# MainBoardV2.net
KiCad netlist of a schematic drawn in EAGLE
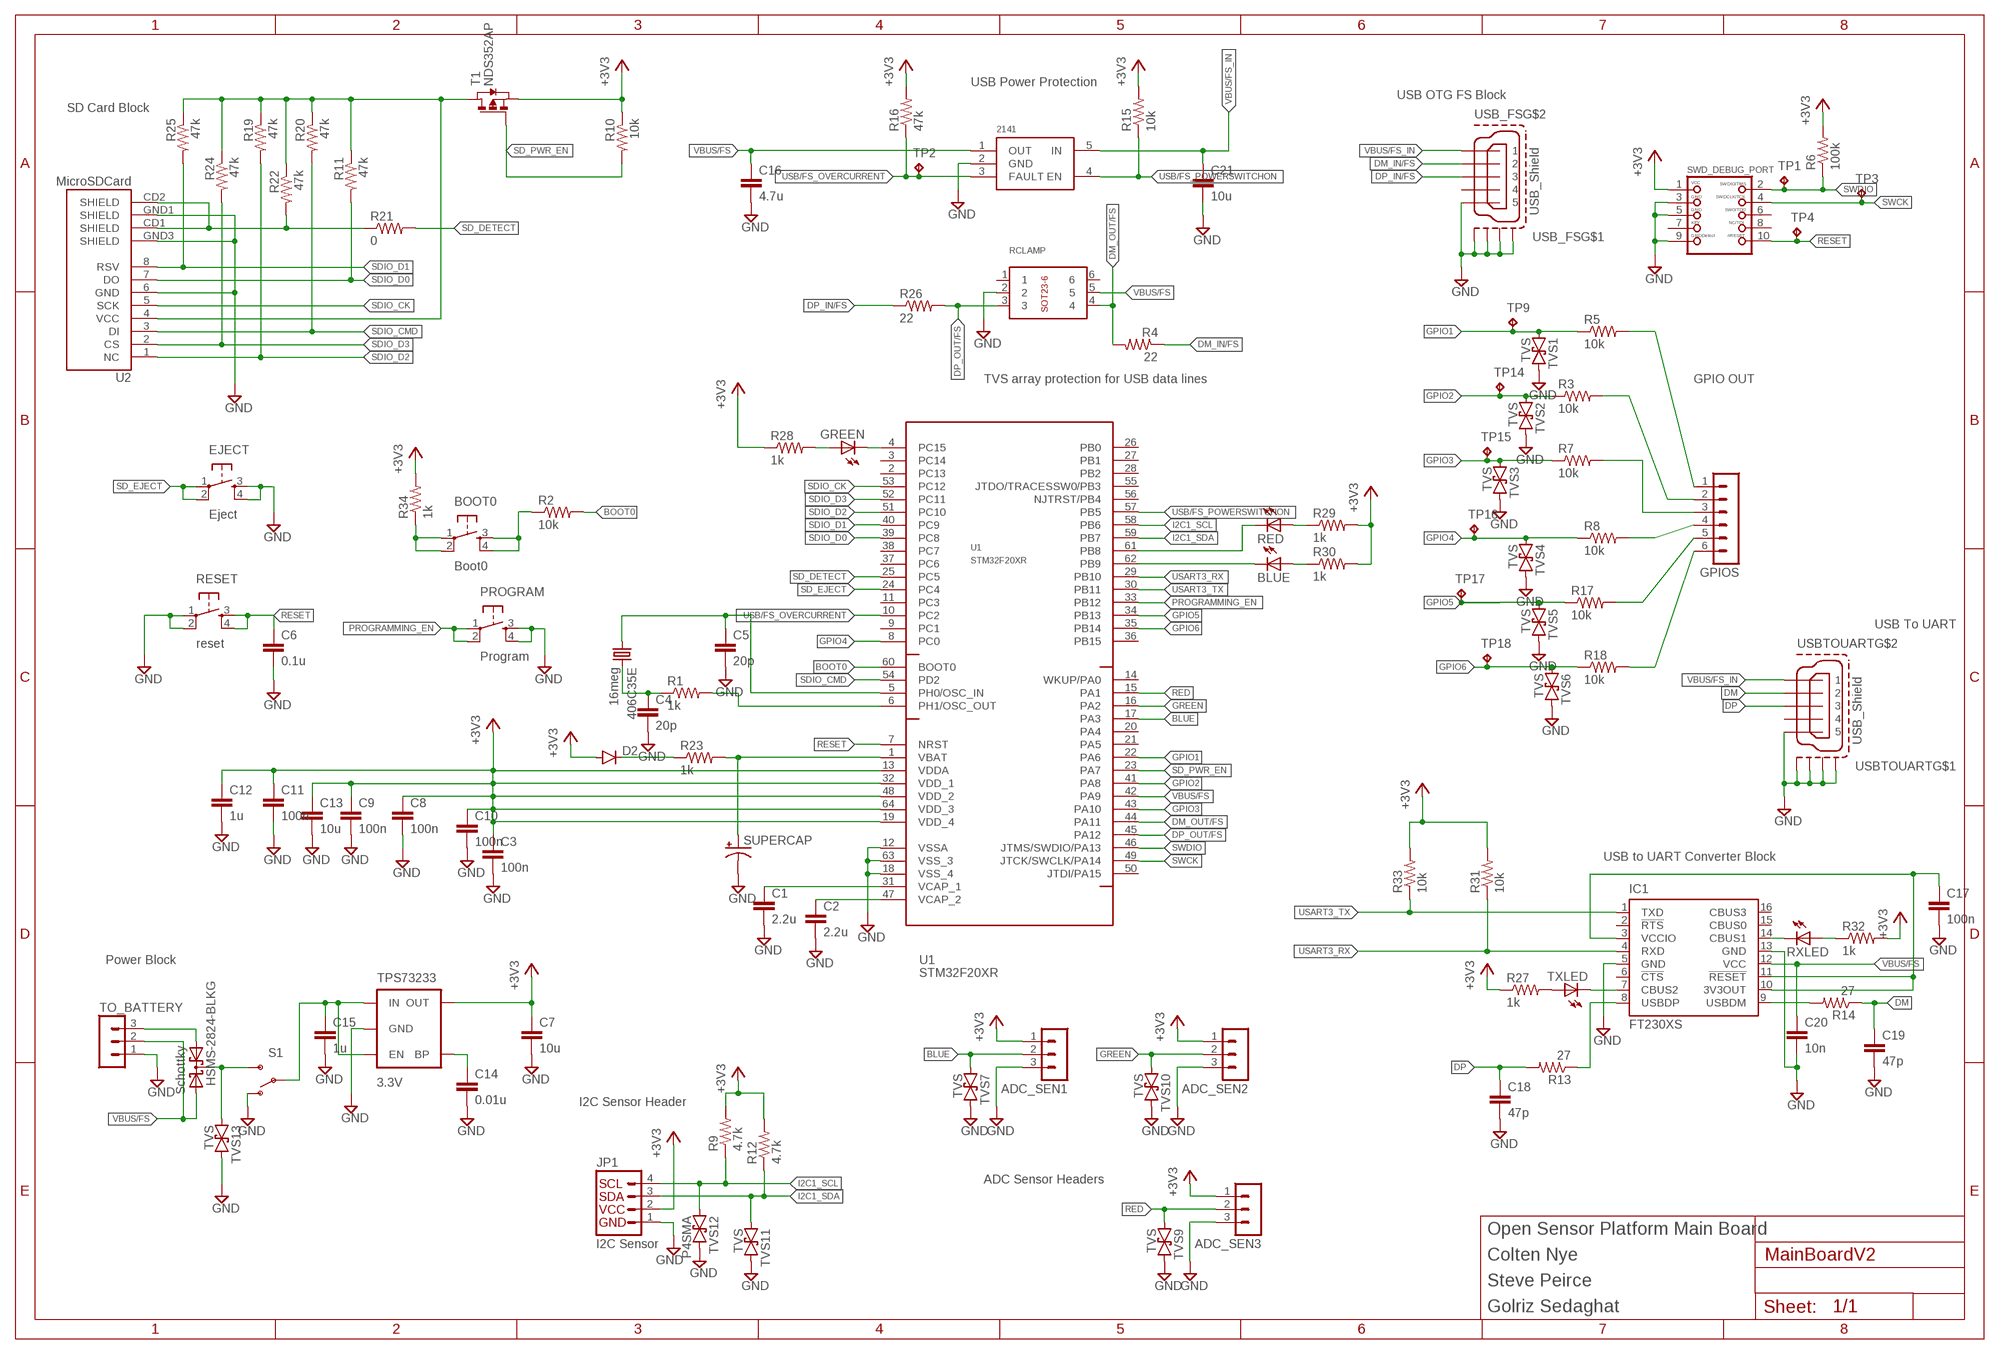
[diagram p0: schematic, sheet 1]

(export (version "E")
  (design (tool "Eeschema 10.0.6"))
  (components
    (comp (ref "406C35E")
      (value "16meg")
      (footprint "eagle-import:CTS406")
      (libsource (lib "eagle-import") (part "CRYSTALCTS406"))
    )
    (comp (ref "2141")
      (value "NCP1400A_STEPUP")
      (footprint "eagle-import:SOT23-5")
      (libsource (lib "eagle-import") (part "NCP1400A_STEPUP"))
    )
    (comp (ref "ADC_SEN1")
      (value "MA03-1")
      (footprint "eagle-import:MA03-1")
      (libsource (lib "eagle-import") (part "MA03-1"))
    )
    (comp (ref "ADC_SEN2")
      (value "MA03-1")
      (footprint "eagle-import:MA03-1")
      (libsource (lib "eagle-import") (part "MA03-1"))
    )
    (comp (ref "ADC_SEN3")
      (value "MA03-1")
      (footprint "eagle-import:MA03-1")
      (libsource (lib "eagle-import") (part "MA03-1"))
    )
    (comp (ref "BLUE")
      (value "LEDSML0805")
      (footprint "eagle-import:SML0805")
      (libsource (lib "eagle-import") (part "LEDSML0805"))
    )
    (comp (ref "BOOT0")
      (value "Boot0")
      (footprint "eagle-import:TACTILE-SWITCH-SMD")
      (libsource (lib "eagle-import") (part "TAC_SWITCHSMD"))
    )
    (comp (ref "C1")
      (value "2.2u")
      (footprint "eagle-import:C0805")
      (libsource (lib "eagle-import") (part "C-EUC0805"))
    )
    (comp (ref "C2")
      (value "2.2u")
      (footprint "eagle-import:C0805")
      (libsource (lib "eagle-import") (part "C-EUC0805"))
    )
    (comp (ref "C3")
      (value "100n")
      (footprint "eagle-import:C0805")
      (libsource (lib "eagle-import") (part "C-EUC0805"))
    )
    (comp (ref "C4")
      (value "20p")
      (footprint "eagle-import:C0805")
      (libsource (lib "eagle-import") (part "C-EUC0805"))
    )
    (comp (ref "C5")
      (value "20p")
      (footprint "eagle-import:C0805")
      (libsource (lib "eagle-import") (part "C-EUC0805"))
    )
    (comp (ref "C6")
      (value "0.1u")
      (footprint "eagle-import:C0805")
      (libsource (lib "eagle-import") (part "C-EUC0805"))
    )
    (comp (ref "C7")
      (value "10u")
      (footprint "eagle-import:C0805")
      (libsource (lib "eagle-import") (part "C-EUC0805"))
    )
    (comp (ref "C8")
      (value "100n")
      (footprint "eagle-import:C0805")
      (libsource (lib "eagle-import") (part "C-EUC0805"))
    )
    (comp (ref "C9")
      (value "100n")
      (footprint "eagle-import:C0805")
      (libsource (lib "eagle-import") (part "C-EUC0805"))
    )
    (comp (ref "C10")
      (value "100n")
      (footprint "eagle-import:C0805")
      (libsource (lib "eagle-import") (part "C-EUC0805"))
    )
    (comp (ref "C11")
      (value "100n")
      (footprint "eagle-import:C0805")
      (libsource (lib "eagle-import") (part "C-EUC0805"))
    )
    (comp (ref "C12")
      (value "1u")
      (footprint "eagle-import:C0805")
      (libsource (lib "eagle-import") (part "C-EUC0805"))
    )
    (comp (ref "C13")
      (value "10u")
      (footprint "eagle-import:C0805")
      (libsource (lib "eagle-import") (part "C-EUC0805"))
    )
    (comp (ref "C14")
      (value "0.01u")
      (footprint "eagle-import:C0805")
      (libsource (lib "eagle-import") (part "C-EUC0805"))
    )
    (comp (ref "C15")
      (value "1u")
      (footprint "eagle-import:C0805")
      (libsource (lib "eagle-import") (part "C-EUC0805"))
    )
    (comp (ref "C16")
      (value "4.7u")
      (footprint "eagle-import:C0805")
      (libsource (lib "eagle-import") (part "C-EUC0805"))
    )
    (comp (ref "C17")
      (value "100n")
      (footprint "eagle-import:C0805")
      (libsource (lib "eagle-import") (part "C-EUC0805"))
    )
    (comp (ref "C18")
      (value "47p")
      (footprint "eagle-import:C0805")
      (libsource (lib "eagle-import") (part "C-EUC0805"))
    )
    (comp (ref "C19")
      (value "47p")
      (footprint "eagle-import:C0805")
      (libsource (lib "eagle-import") (part "C-EUC0805"))
    )
    (comp (ref "C20")
      (value "10n")
      (footprint "eagle-import:C0805")
      (libsource (lib "eagle-import") (part "C-EUC0805"))
    )
    (comp (ref "C21")
      (value "10u")
      (footprint "eagle-import:C0805")
      (libsource (lib "eagle-import") (part "C-EUC0805"))
    )
    (comp (ref "D2")
      (value "DIODESMA")
      (footprint "eagle-import:SMA-DIODE")
      (libsource (lib "eagle-import") (part "DIODESMA"))
    )
    (comp (ref "EJECT")
      (value "Eject")
      (footprint "eagle-import:TACTILE-SWITCH-SMD")
      (libsource (lib "eagle-import") (part "TAC_SWITCHSMD"))
    )
    (comp (ref "GPIOS")
      (value "MA06-1")
      (footprint "eagle-import:MA06-1")
      (libsource (lib "eagle-import") (part "MA06-1"))
    )
    (comp (ref "GREEN")
      (value "LEDSML0805")
      (footprint "eagle-import:SML0805")
      (libsource (lib "eagle-import") (part "LEDSML0805"))
    )
    (comp (ref "HSMS-2824-BLKG")
      (value "Schottky")
      (footprint "eagle-import:SOT23")
      (libsource (lib "eagle-import") (part "BAS70-05"))
    )
    (comp (ref "IC1")
      (value "FT230XS")
      (footprint "eagle-import:SSOP16")
      (libsource (lib "eagle-import") (part "FT230XS"))
    )
    (comp (ref "JP1")
      (value "I2C Sensor")
      (footprint "eagle-import:1X04")
      (libsource (lib "eagle-import") (part "I2C_STANDARD"))
    )
    (comp (ref "PROGRAM")
      (value "Program")
      (footprint "eagle-import:TACTILE-SWITCH-SMD")
      (libsource (lib "eagle-import") (part "TAC_SWITCHSMD"))
    )
    (comp (ref "R1")
      (value "1k")
      (footprint "eagle-import:R0805")
      (libsource (lib "eagle-import") (part "R-US_R0805"))
    )
    (comp (ref "R2")
      (value "10k")
      (footprint "eagle-import:R0805")
      (libsource (lib "eagle-import") (part "R-US_R0805"))
    )
    (comp (ref "R3")
      (value "10k")
      (footprint "eagle-import:R0805")
      (libsource (lib "eagle-import") (part "R-US_R0805"))
    )
    (comp (ref "R4")
      (value "22")
      (footprint "eagle-import:R0805")
      (libsource (lib "eagle-import") (part "R-US_R0805"))
    )
    (comp (ref "R5")
      (value "10k")
      (footprint "eagle-import:R0805")
      (libsource (lib "eagle-import") (part "R-US_R0805"))
    )
    (comp (ref "R6")
      (value "100k")
      (footprint "eagle-import:R0805")
      (libsource (lib "eagle-import") (part "R-US_R0805"))
    )
    (comp (ref "R7")
      (value "10k")
      (footprint "eagle-import:R0805")
      (libsource (lib "eagle-import") (part "R-US_R0805"))
    )
    (comp (ref "R8")
      (value "10k")
      (footprint "eagle-import:R0805")
      (libsource (lib "eagle-import") (part "R-US_R0805"))
    )
    (comp (ref "R9")
      (value "4.7k")
      (footprint "eagle-import:R0805")
      (libsource (lib "eagle-import") (part "R-US_R0805"))
    )
    (comp (ref "R10")
      (value "10k")
      (footprint "eagle-import:R0805")
      (libsource (lib "eagle-import") (part "R-US_R0805"))
    )
    (comp (ref "R11")
      (value "47k")
      (footprint "eagle-import:R0805")
      (libsource (lib "eagle-import") (part "R-US_R0805"))
    )
    (comp (ref "R12")
      (value "4.7k")
      (footprint "eagle-import:R0805")
      (libsource (lib "eagle-import") (part "R-US_R0805"))
    )
    (comp (ref "R13")
      (value "27")
      (footprint "eagle-import:R0805")
      (libsource (lib "eagle-import") (part "R-US_R0805"))
    )
    (comp (ref "R14")
      (value "27")
      (footprint "eagle-import:R0805")
      (libsource (lib "eagle-import") (part "R-US_R0805"))
    )
    (comp (ref "R15")
      (value "10k")
      (footprint "eagle-import:R0805")
      (libsource (lib "eagle-import") (part "R-US_R0805"))
    )
    (comp (ref "R16")
      (value "47k")
      (footprint "eagle-import:R0805")
      (libsource (lib "eagle-import") (part "R-US_R0805"))
    )
    (comp (ref "R17")
      (value "10k")
      (footprint "eagle-import:R0805")
      (libsource (lib "eagle-import") (part "R-US_R0805"))
    )
    (comp (ref "R18")
      (value "10k")
      (footprint "eagle-import:R0805")
      (libsource (lib "eagle-import") (part "R-US_R0805"))
    )
    (comp (ref "R19")
      (value "47k")
      (footprint "eagle-import:R0805")
      (libsource (lib "eagle-import") (part "R-US_R0805"))
    )
    (comp (ref "R20")
      (value "47k")
      (footprint "eagle-import:R0805")
      (libsource (lib "eagle-import") (part "R-US_R0805"))
    )
    (comp (ref "R21")
      (value "0")
      (footprint "eagle-import:R0805")
      (libsource (lib "eagle-import") (part "R-US_R0805"))
    )
    (comp (ref "R22")
      (value "47k")
      (footprint "eagle-import:R0805")
      (libsource (lib "eagle-import") (part "R-US_R0805"))
    )
    (comp (ref "R23")
      (value "1k")
      (footprint "eagle-import:R0805")
      (libsource (lib "eagle-import") (part "R-US_R0805"))
    )
    (comp (ref "R24")
      (value "47k")
      (footprint "eagle-import:R0805")
      (libsource (lib "eagle-import") (part "R-US_R0805"))
    )
    (comp (ref "R25")
      (value "47k")
      (footprint "eagle-import:R0805")
      (libsource (lib "eagle-import") (part "R-US_R0805"))
    )
    (comp (ref "R26")
      (value "22")
      (footprint "eagle-import:R0805")
      (libsource (lib "eagle-import") (part "R-US_R0805"))
    )
    (comp (ref "R27")
      (value "1k")
      (footprint "eagle-import:R0805")
      (libsource (lib "eagle-import") (part "R-US_R0805"))
    )
    (comp (ref "R28")
      (value "1k")
      (footprint "eagle-import:R0805")
      (libsource (lib "eagle-import") (part "R-US_R0805"))
    )
    (comp (ref "R29")
      (value "1k")
      (footprint "eagle-import:R0805")
      (libsource (lib "eagle-import") (part "R-US_R0805"))
    )
    (comp (ref "R30")
      (value "1k")
      (footprint "eagle-import:R0805")
      (libsource (lib "eagle-import") (part "R-US_R0805"))
    )
    (comp (ref "R31")
      (value "10k")
      (footprint "eagle-import:R0805")
      (libsource (lib "eagle-import") (part "R-US_R0805"))
    )
    (comp (ref "R32")
      (value "1k")
      (footprint "eagle-import:R0805")
      (libsource (lib "eagle-import") (part "R-US_R0805"))
    )
    (comp (ref "R33")
      (value "10k")
      (footprint "eagle-import:R0805")
      (libsource (lib "eagle-import") (part "R-US_R0805"))
    )
    (comp (ref "R34")
      (value "1k")
      (footprint "eagle-import:R0805")
      (libsource (lib "eagle-import") (part "R-US_R0805"))
    )
    (comp (ref "RCLAMP")
      (value "BREAKOUT_SOT23-6")
      (footprint "eagle-import:BREAKOUT_SOT23-6")
      (libsource (lib "eagle-import") (part "BREAKOUT_SOT23-6"))
    )
    (comp (ref "RED")
      (value "LEDSML0805")
      (footprint "eagle-import:SML0805")
      (libsource (lib "eagle-import") (part "LEDSML0805"))
    )
    (comp (ref "RESET")
      (value "reset")
      (footprint "eagle-import:TACTILE-SWITCH-SMD")
      (libsource (lib "eagle-import") (part "TAC_SWITCHSMD"))
    )
    (comp (ref "RXLED")
      (value "LEDSML0805")
      (footprint "eagle-import:SML0805")
      (libsource (lib "eagle-import") (part "LEDSML0805"))
    )
    (comp (ref "S1")
      (value "SWITCH-SPDTSMD")
      (footprint "eagle-import:AYZ0202")
      (libsource (lib "eagle-import") (part "SWITCH-SPDTSMD"))
    )
    (comp (ref "SUPERCAP")
      (value "SUPERCAP")
      (footprint "eagle-import:414-VA5R")
      (libsource (lib "eagle-import") (part "SUPERCAP"))
    )
    (comp (ref "SWD_DEBUG_PORT")
      (value "JTAG-CORTEXM3")
      (footprint "eagle-import:2X05_1.27MM_SMT")
      (libsource (lib "eagle-import") (part "JTAG-CORTEXM3"))
    )
    (comp (ref "T1")
      (value "NDS352AP")
      (footprint "eagle-import:SOT-23")
      (libsource (lib "eagle-import") (part "PMOSSOT23"))
    )
    (comp (ref "TO_BATTERY")
      (value "MA03-1")
      (footprint "eagle-import:MA03-1")
      (libsource (lib "eagle-import") (part "MA03-1"))
    )
    (comp (ref "TP1")
      (value "TPB1,27")
      (footprint "eagle-import:B1,27")
      (libsource (lib "eagle-import") (part "TPB1,27"))
    )
    (comp (ref "TP2")
      (value "TPB1,27")
      (footprint "eagle-import:B1,27")
      (libsource (lib "eagle-import") (part "TPB1,27"))
    )
    (comp (ref "TP3")
      (value "TPB1,27")
      (footprint "eagle-import:B1,27")
      (libsource (lib "eagle-import") (part "TPB1,27"))
    )
    (comp (ref "TP4")
      (value "TPB1,27")
      (footprint "eagle-import:B1,27")
      (libsource (lib "eagle-import") (part "TPB1,27"))
    )
    (comp (ref "TP9")
      (value "TPB1,27")
      (footprint "eagle-import:B1,27")
      (libsource (lib "eagle-import") (part "TPB1,27"))
    )
    (comp (ref "TP14")
      (value "TPB1,27")
      (footprint "eagle-import:B1,27")
      (libsource (lib "eagle-import") (part "TPB1,27"))
    )
    (comp (ref "TP15")
      (value "TPB1,27")
      (footprint "eagle-import:B1,27")
      (libsource (lib "eagle-import") (part "TPB1,27"))
    )
    (comp (ref "TP16")
      (value "TPB1,27")
      (footprint "eagle-import:B1,27")
      (libsource (lib "eagle-import") (part "TPB1,27"))
    )
    (comp (ref "TP17")
      (value "TPB1,27")
      (footprint "eagle-import:B1,27")
      (libsource (lib "eagle-import") (part "TPB1,27"))
    )
    (comp (ref "TP18")
      (value "TPB1,27")
      (footprint "eagle-import:B1,27")
      (libsource (lib "eagle-import") (part "TPB1,27"))
    )
    (comp (ref "TPS73233")
      (value "3.3V")
      (footprint "eagle-import:SOT23-5")
      (libsource (lib "eagle-import") (part "V_REG_MIC52053.3V"))
    )
    (comp (ref "TVS1")
      (value "TVS")
      (footprint "eagle-import:SMA-DIODE")
      (libsource (lib "eagle-import") (part "TVS"))
    )
    (comp (ref "TVS2")
      (value "TVS")
      (footprint "eagle-import:SMA-DIODE")
      (libsource (lib "eagle-import") (part "TVS"))
    )
    (comp (ref "TVS3")
      (value "TVS")
      (footprint "eagle-import:SMA-DIODE")
      (libsource (lib "eagle-import") (part "TVS"))
    )
    (comp (ref "TVS4")
      (value "TVS")
      (footprint "eagle-import:SMA-DIODE")
      (libsource (lib "eagle-import") (part "TVS"))
    )
    (comp (ref "TVS5")
      (value "TVS")
      (footprint "eagle-import:SMA-DIODE")
      (libsource (lib "eagle-import") (part "TVS"))
    )
    (comp (ref "TVS6")
      (value "TVS")
      (footprint "eagle-import:SMA-DIODE")
      (libsource (lib "eagle-import") (part "TVS"))
    )
    (comp (ref "TVS7")
      (value "TVS")
      (footprint "eagle-import:SMA-DIODE")
      (libsource (lib "eagle-import") (part "TVS"))
    )
    (comp (ref "TVS9")
      (value "TVS")
      (footprint "eagle-import:SMA-DIODE")
      (libsource (lib "eagle-import") (part "TVS"))
    )
    (comp (ref "TVS10")
      (value "TVS")
      (footprint "eagle-import:SMA-DIODE")
      (libsource (lib "eagle-import") (part "TVS"))
    )
    (comp (ref "TVS11")
      (value "TVS")
      (footprint "eagle-import:SMA-DIODE")
      (libsource (lib "eagle-import") (part "TVS"))
    )
    (comp (ref "TVS12")
      (value "P4SMA")
      (footprint "eagle-import:SMA-DIODE")
      (libsource (lib "eagle-import") (part "TVS"))
    )
    (comp (ref "TVS13")
      (value "TVS")
      (footprint "eagle-import:SMA-DIODE")
      (libsource (lib "eagle-import") (part "TVS"))
    )
    (comp (ref "TXLED")
      (value "LEDSML0805")
      (footprint "eagle-import:SML0805")
      (libsource (lib "eagle-import") (part "LEDSML0805"))
    )
    (comp (ref "U1")
      (value "STM32F20XR")
      (footprint "eagle-import:LQFP64")
      (libsource (lib "eagle-import") (part "STM32F20XR"))
    )
    (comp (ref "U2")
      (value "MicroSDCard")
      (footprint "eagle-import:MICRO-SD-SOCKET-PP")
      (libsource (lib "eagle-import") (part "USD-SOCKETNEW"))
    )
    (comp (ref "USBTOUART")
      (value "USB_Shield")
      (footprint "eagle-import:ZX62R-B-5P")
      (libsource (lib "eagle-import") (part "MICRO-USB-SHIELD-ZX62R-B-5P"))
    )
    (comp (ref "USB_FS")
      (value "USB_Shield")
      (footprint "eagle-import:ZX62R-B-5P")
      (libsource (lib "eagle-import") (part "MICRO-USB-SHIELD-ZX62R-B-5P"))
    )
  )
  (nets
    (net (code "1") (name "+3V3") (class "Default")
      (node (ref "ADC_SEN1") (pin "1") (pinfunction "1_1") (pintype "passive"))
      (node (ref "ADC_SEN2") (pin "1") (pinfunction "1_1") (pintype "passive"))
      (node (ref "ADC_SEN3") (pin "1") (pinfunction "1_1") (pintype "passive"))
      (node (ref "C10") (pin "1") (pinfunction "1_1") (pintype "passive"))
      (node (ref "C11") (pin "1") (pinfunction "1_1") (pintype "passive"))
      (node (ref "C12") (pin "1") (pinfunction "1_1") (pintype "passive"))
      (node (ref "C13") (pin "1") (pinfunction "1_1") (pintype "passive"))
      (node (ref "C3") (pin "1") (pinfunction "1_1") (pintype "passive"))
      (node (ref "C7") (pin "1") (pinfunction "1_1") (pintype "passive"))
      (node (ref "C8") (pin "1") (pinfunction "1_1") (pintype "passive"))
      (node (ref "C9") (pin "1") (pinfunction "1_1") (pintype "passive"))
      (node (ref "D2") (pin "A") (pinfunction "A_A") (pintype "passive"))
      (node (ref "JP1") (pin "2") (pinfunction "2_2") (pintype "passive"))
      (node (ref "R10") (pin "1") (pinfunction "1_1") (pintype "passive"))
      (node (ref "R12") (pin "2") (pinfunction "2_2") (pintype "passive"))
      (node (ref "R15") (pin "2") (pinfunction "2_2") (pintype "passive"))
      (node (ref "R16") (pin "2") (pinfunction "2_2") (pintype "passive"))
      (node (ref "R27") (pin "1") (pinfunction "1_1") (pintype "passive"))
      (node (ref "R28") (pin "1") (pinfunction "1_1") (pintype "passive"))
      (node (ref "R29") (pin "2") (pinfunction "2_2") (pintype "passive"))
      (node (ref "R30") (pin "2") (pinfunction "2_2") (pintype "passive"))
      (node (ref "R31") (pin "2") (pinfunction "2_2") (pintype "passive"))
      (node (ref "R32") (pin "2") (pinfunction "2_2") (pintype "passive"))
      (node (ref "R33") (pin "2") (pinfunction "2_2") (pintype "passive"))
      (node (ref "R34") (pin "2") (pinfunction "2_2") (pintype "passive"))
      (node (ref "R6") (pin "2") (pinfunction "2_2") (pintype "passive"))
      (node (ref "R9") (pin "2") (pinfunction "2_2") (pintype "passive"))
      (node (ref "SWD_DEBUG_PORT") (pin "1") (pinfunction "1_1") (pintype "passive"))
      (node (ref "T1") (pin "2") (pinfunction "S_2") (pintype "passive"))
      (node (ref "TPS73233") (pin "5") (pinfunction "OUT_5") (pintype "passive"))
      (node (ref "U1") (pin "13") (pinfunction "VDDA_13") (pintype "power_in"))
      (node (ref "U1") (pin "19") (pinfunction "VDD_4_19") (pintype "power_in"))
      (node (ref "U1") (pin "32") (pinfunction "VDD_1_32") (pintype "power_in"))
      (node (ref "U1") (pin "48") (pinfunction "VDD_2_48") (pintype "power_in"))
      (node (ref "U1") (pin "64") (pinfunction "VDD_3_64") (pintype "power_in"))
    )
    (net (code "2") (name "BLUE") (class "Default")
      (node (ref "ADC_SEN1") (pin "2") (pinfunction "2_2") (pintype "passive"))
      (node (ref "TVS7") (pin "A") (pinfunction "1_A") (pintype "passive"))
      (node (ref "U1") (pin "17") (pinfunction "PA3_17") (pintype "bidirectional"))
    )
    (net (code "3") (name "BOOT0") (class "Default")
      (node (ref "R2") (pin "2") (pinfunction "2_2") (pintype "passive"))
      (node (ref "U1") (pin "60") (pinfunction "BOOT0_60") (pintype "bidirectional"))
    )
    (net (code "4") (name "DM") (class "Default")
      (node (ref "C19") (pin "1") (pinfunction "1_1") (pintype "passive"))
      (node (ref "R14") (pin "1") (pinfunction "1_1") (pintype "passive"))
      (node (ref "USBTOUART") (pin "2") (pinfunction "2_2") (pintype "input"))
    )
    (net (code "5") (name "DM_IN{slash}FS") (class "Default")
      (node (ref "R4") (pin "1") (pinfunction "1_1") (pintype "passive"))
      (node (ref "USB_FS") (pin "2") (pinfunction "2_2") (pintype "input"))
    )
    (net (code "6") (name "DM_OUT{slash}FS") (class "Default")
      (node (ref "R4") (pin "2") (pinfunction "2_2") (pintype "passive"))
      (node (ref "RCLAMP") (pin "4") (pinfunction "4_4") (pintype "bidirectional"))
      (node (ref "U1") (pin "44") (pinfunction "PA11_44") (pintype "bidirectional"))
    )
    (net (code "7") (name "DP") (class "Default")
      (node (ref "C18") (pin "1") (pinfunction "1_1") (pintype "passive"))
      (node (ref "R13") (pin "2") (pinfunction "2_2") (pintype "passive"))
      (node (ref "USBTOUART") (pin "3") (pinfunction "3_3") (pintype "input"))
    )
    (net (code "8") (name "DP_IN{slash}FS") (class "Default")
      (node (ref "R26") (pin "1") (pinfunction "1_1") (pintype "passive"))
      (node (ref "USB_FS") (pin "3") (pinfunction "3_3") (pintype "input"))
    )
    (net (code "9") (name "DP_OUT{slash}FS") (class "Default")
      (node (ref "R26") (pin "2") (pinfunction "2_2") (pintype "passive"))
      (node (ref "RCLAMP") (pin "3") (pinfunction "3_3") (pintype "bidirectional"))
      (node (ref "U1") (pin "45") (pinfunction "PA12_45") (pintype "bidirectional"))
    )
    (net (code "10") (name "GND") (class "Default")
      (node (ref "2141") (pin "2") (pinfunction "GND_2") (pintype "bidirectional"))
      (node (ref "ADC_SEN1") (pin "3") (pinfunction "3_3") (pintype "passive"))
      (node (ref "ADC_SEN2") (pin "3") (pinfunction "3_3") (pintype "passive"))
      (node (ref "ADC_SEN3") (pin "3") (pinfunction "3_3") (pintype "passive"))
      (node (ref "C1") (pin "2") (pinfunction "2_2") (pintype "passive"))
      (node (ref "C10") (pin "2") (pinfunction "2_2") (pintype "passive"))
      (node (ref "C11") (pin "2") (pinfunction "2_2") (pintype "passive"))
      (node (ref "C12") (pin "2") (pinfunction "2_2") (pintype "passive"))
      (node (ref "C13") (pin "2") (pinfunction "2_2") (pintype "passive"))
      (node (ref "C14") (pin "2") (pinfunction "2_2") (pintype "passive"))
      (node (ref "C15") (pin "2") (pinfunction "2_2") (pintype "passive"))
      (node (ref "C16") (pin "2") (pinfunction "2_2") (pintype "passive"))
      (node (ref "C17") (pin "2") (pinfunction "2_2") (pintype "passive"))
      (node (ref "C18") (pin "2") (pinfunction "2_2") (pintype "passive"))
      (node (ref "C19") (pin "2") (pinfunction "2_2") (pintype "passive"))
      (node (ref "C2") (pin "2") (pinfunction "2_2") (pintype "passive"))
      (node (ref "C20") (pin "2") (pinfunction "2_2") (pintype "passive"))
      (node (ref "C21") (pin "2") (pinfunction "2_2") (pintype "passive"))
      (node (ref "C3") (pin "2") (pinfunction "2_2") (pintype "passive"))
      (node (ref "C4") (pin "2") (pinfunction "2_2") (pintype "passive"))
      (node (ref "C5") (pin "2") (pinfunction "2_2") (pintype "passive"))
      (node (ref "C6") (pin "2") (pinfunction "2_2") (pintype "passive"))
      (node (ref "C7") (pin "2") (pinfunction "2_2") (pintype "passive"))
      (node (ref "C8") (pin "2") (pinfunction "2_2") (pintype "passive"))
      (node (ref "C9") (pin "2") (pinfunction "2_2") (pintype "passive"))
      (node (ref "EJECT") (pin "3") (pinfunction "3_3") (pintype "passive"))
      (node (ref "EJECT") (pin "4") (pinfunction "4_4") (pintype "passive"))
      (node (ref "IC1") (pin "13") (pinfunction "GND_13") (pintype "power_in"))
      (node (ref "IC1") (pin "5") (pinfunction "GND_5") (pintype "power_in"))
      (node (ref "JP1") (pin "1") (pinfunction "1_1") (pintype "passive"))
      (node (ref "PROGRAM") (pin "3") (pinfunction "3_3") (pintype "passive"))
      (node (ref "PROGRAM") (pin "4") (pinfunction "4_4") (pintype "passive"))
      (node (ref "RCLAMP") (pin "2") (pinfunction "2_2") (pintype "bidirectional"))
      (node (ref "RESET") (pin "1") (pinfunction "1_1") (pintype "passive"))
      (node (ref "RESET") (pin "2") (pinfunction "2_2") (pintype "passive"))
      (node (ref "S1") (pin "1") (pinfunction "O_1") (pintype "passive"))
      (node (ref "SUPERCAP") (pin "-") (pinfunction "-_-") (pintype "passive"))
      (node (ref "SWD_DEBUG_PORT") (pin "3") (pinfunction "3_3") (pintype "passive"))
      (node (ref "SWD_DEBUG_PORT") (pin "5") (pinfunction "5_5") (pintype "passive"))
      (node (ref "SWD_DEBUG_PORT") (pin "9") (pinfunction "9_9") (pintype "passive"))
      (node (ref "TO_BATTERY") (pin "1") (pinfunction "1_1") (pintype "passive"))
      (node (ref "TPS73233") (pin "2") (pinfunction "GND_2") (pintype "input"))
      (node (ref "TVS1") (pin "C") (pinfunction "2_C") (pintype "passive"))
      (node (ref "TVS10") (pin "C") (pinfunction "2_C") (pintype "passive"))
      (node (ref "TVS11") (pin "C") (pinfunction "2_C") (pintype "passive"))
      (node (ref "TVS12") (pin "C") (pinfunction "2_C") (pintype "passive"))
      (node (ref "TVS13") (pin "C") (pinfunction "2_C") (pintype "passive"))
      (node (ref "TVS2") (pin "C") (pinfunction "2_C") (pintype "passive"))
      (node (ref "TVS3") (pin "C") (pinfunction "2_C") (pintype "passive"))
      (node (ref "TVS4") (pin "C") (pinfunction "2_C") (pintype "passive"))
      (node (ref "TVS5") (pin "C") (pinfunction "2_C") (pintype "passive"))
      (node (ref "TVS6") (pin "C") (pinfunction "2_C") (pintype "passive"))
      (node (ref "TVS7") (pin "C") (pinfunction "2_C") (pintype "passive"))
      (node (ref "TVS9") (pin "C") (pinfunction "2_C") (pintype "passive"))
      (node (ref "U1") (pin "12") (pinfunction "VSSA_12") (pintype "power_in"))
      (node (ref "U1") (pin "18") (pinfunction "VSS_4_18") (pintype "power_in"))
      (node (ref "U1") (pin "63") (pinfunction "VSS_3_63") (pintype "power_in"))
      (node (ref "U2") (pin "6") (pinfunction "GND_6") (pintype "bidirectional"))
      (node (ref "U2") (pin "GND1") (pinfunction "SHIELD_GND1") (pintype "bidirectional"))
      (node (ref "U2") (pin "GND3") (pinfunction "SHIELD_GND3") (pintype "bidirectional"))
      (node (ref "USBTOUART") (pin "5") (pinfunction "5_5") (pintype "input"))
      (node (ref "USBTOUART") (pin "M1") (pinfunction "S1_M1") (pintype "passive"))
      (node (ref "USBTOUART") (pin "M2") (pinfunction "S2_M2") (pintype "passive"))
      (node (ref "USBTOUART") (pin "M3") (pinfunction "S3_M3") (pintype "passive"))
      (node (ref "USBTOUART") (pin "M4") (pinfunction "S4_M4") (pintype "passive"))
      (node (ref "USB_FS") (pin "5") (pinfunction "5_5") (pintype "input"))
      (node (ref "USB_FS") (pin "M1") (pinfunction "S1_M1") (pintype "passive"))
      (node (ref "USB_FS") (pin "M2") (pinfunction "S2_M2") (pintype "passive"))
      (node (ref "USB_FS") (pin "M3") (pinfunction "S3_M3") (pintype "passive"))
      (node (ref "USB_FS") (pin "M4") (pinfunction "S4_M4") (pintype "passive"))
    )
    (net (code "11") (name "GPIO1") (class "Default")
      (node (ref "R5") (pin "1") (pinfunction "1_1") (pintype "passive"))
      (node (ref "TP9") (pin "TP") (pinfunction "TP_TP") (pintype "input"))
      (node (ref "TVS1") (pin "A") (pinfunction "1_A") (pintype "passive"))
      (node (ref "U1") (pin "22") (pinfunction "PA6_22") (pintype "bidirectional"))
    )
    (net (code "12") (name "GPIO2") (class "Default")
      (node (ref "R3") (pin "1") (pinfunction "1_1") (pintype "passive"))
      (node (ref "TP14") (pin "TP") (pinfunction "TP_TP") (pintype "input"))
      (node (ref "TVS2") (pin "A") (pinfunction "1_A") (pintype "passive"))
      (node (ref "U1") (pin "41") (pinfunction "PA8_41") (pintype "bidirectional"))
    )
    (net (code "13") (name "GPIO3") (class "Default")
      (node (ref "R7") (pin "1") (pinfunction "1_1") (pintype "passive"))
      (node (ref "TP15") (pin "TP") (pinfunction "TP_TP") (pintype "input"))
      (node (ref "TVS3") (pin "A") (pinfunction "1_A") (pintype "passive"))
      (node (ref "U1") (pin "43") (pinfunction "PA10_43") (pintype "bidirectional"))
    )
    (net (code "14") (name "GPIO4") (class "Default")
      (node (ref "R8") (pin "1") (pinfunction "1_1") (pintype "passive"))
      (node (ref "TP16") (pin "TP") (pinfunction "TP_TP") (pintype "input"))
      (node (ref "TVS4") (pin "A") (pinfunction "1_A") (pintype "passive"))
      (node (ref "U1") (pin "8") (pinfunction "PC0_8") (pintype "bidirectional"))
    )
    (net (code "15") (name "GPIO5") (class "Default")
      (node (ref "R17") (pin "1") (pinfunction "1_1") (pintype "passive"))
      (node (ref "TP17") (pin "TP") (pinfunction "TP_TP") (pintype "input"))
      (node (ref "TVS5") (pin "A") (pinfunction "1_A") (pintype "passive"))
      (node (ref "U1") (pin "34") (pinfunction "PB13_34") (pintype "bidirectional"))
    )
    (net (code "16") (name "GPIO6") (class "Default")
      (node (ref "R18") (pin "1") (pinfunction "1_1") (pintype "passive"))
      (node (ref "TP18") (pin "TP") (pinfunction "TP_TP") (pintype "input"))
      (node (ref "TVS6") (pin "A") (pinfunction "1_A") (pintype "passive"))
      (node (ref "U1") (pin "35") (pinfunction "PB14_35") (pintype "bidirectional"))
    )
    (net (code "17") (name "GREEN") (class "Default")
      (node (ref "ADC_SEN2") (pin "2") (pinfunction "2_2") (pintype "passive"))
      (node (ref "TVS10") (pin "A") (pinfunction "1_A") (pintype "passive"))
      (node (ref "U1") (pin "16") (pinfunction "PA2_16") (pintype "bidirectional"))
    )
    (net (code "18") (name "I2C1_SCL") (class "Default")
      (node (ref "JP1") (pin "4") (pinfunction "4_4") (pintype "passive"))
      (node (ref "R9") (pin "1") (pinfunction "1_1") (pintype "passive"))
      (node (ref "TVS12") (pin "A") (pinfunction "1_A") (pintype "passive"))
      (node (ref "U1") (pin "58") (pinfunction "PB6_58") (pintype "bidirectional"))
    )
    (net (code "19") (name "I2C1_SDA") (class "Default")
      (node (ref "JP1") (pin "3") (pinfunction "3_3") (pintype "passive"))
      (node (ref "R12") (pin "1") (pinfunction "1_1") (pintype "passive"))
      (node (ref "TVS11") (pin "A") (pinfunction "1_A") (pintype "passive"))
      (node (ref "U1") (pin "59") (pinfunction "PB7_59") (pintype "bidirectional"))
    )
    (net (code "20") (name "Net-(406C35E-2)") (class "Default")
      (node (ref "406C35E") (pin "3") (pinfunction "2_3") (pintype "passive"))
      (node (ref "C4") (pin "1") (pinfunction "1_1") (pintype "passive"))
      (node (ref "R1") (pin "1") (pinfunction "1_1") (pintype "passive"))
    )
    (net (code "21") (name "Net-(BLUE-PadA)") (class "Default")
      (node (ref "BLUE") (pin "A") (pinfunction "A_A") (pintype "passive"))
      (node (ref "R30") (pin "1") (pinfunction "1_1") (pintype "passive"))
    )
    (net (code "22") (name "Net-(BOOT0-Pad1)") (class "Default")
      (node (ref "BOOT0") (pin "1") (pinfunction "1_1") (pintype "passive"))
      (node (ref "BOOT0") (pin "2") (pinfunction "2_2") (pintype "passive"))
      (node (ref "R34") (pin "1") (pinfunction "1_1") (pintype "passive"))
    )
    (net (code "23") (name "Net-(BOOT0-Pad3)") (class "Default")
      (node (ref "BOOT0") (pin "3") (pinfunction "3_3") (pintype "passive"))
      (node (ref "BOOT0") (pin "4") (pinfunction "4_4") (pintype "passive"))
      (node (ref "R2") (pin "1") (pinfunction "1_1") (pintype "passive"))
    )
    (net (code "24") (name "Net-(D2-PadC)") (class "Default")
      (node (ref "D2") (pin "C") (pinfunction "C_C") (pintype "passive"))
      (node (ref "R23") (pin "1") (pinfunction "1_1") (pintype "passive"))
    )
    (net (code "25") (name "Net-(GPIOS-Pad1)") (class "Default")
      (node (ref "GPIOS") (pin "1") (pinfunction "1_1") (pintype "passive"))
      (node (ref "R5") (pin "2") (pinfunction "2_2") (pintype "passive"))
    )
    (net (code "26") (name "Net-(GPIOS-Pad2)") (class "Default")
      (node (ref "GPIOS") (pin "2") (pinfunction "2_2") (pintype "passive"))
      (node (ref "R3") (pin "2") (pinfunction "2_2") (pintype "passive"))
    )
    (net (code "27") (name "Net-(GPIOS-Pad3)") (class "Default")
      (node (ref "GPIOS") (pin "3") (pinfunction "3_3") (pintype "passive"))
      (node (ref "R7") (pin "2") (pinfunction "2_2") (pintype "passive"))
    )
    (net (code "28") (name "Net-(GPIOS-Pad4)") (class "Default")
      (node (ref "GPIOS") (pin "4") (pinfunction "4_4") (pintype "passive"))
      (node (ref "R8") (pin "2") (pinfunction "2_2") (pintype "passive"))
    )
    (net (code "29") (name "Net-(GPIOS-Pad5)") (class "Default")
      (node (ref "GPIOS") (pin "5") (pinfunction "5_5") (pintype "passive"))
      (node (ref "R17") (pin "2") (pinfunction "2_2") (pintype "passive"))
    )
    (net (code "30") (name "Net-(GPIOS-Pad6)") (class "Default")
      (node (ref "GPIOS") (pin "6") (pinfunction "6_6") (pintype "passive"))
      (node (ref "R18") (pin "2") (pinfunction "2_2") (pintype "passive"))
    )
    (net (code "31") (name "Net-(GREEN-PadA)") (class "Default")
      (node (ref "GREEN") (pin "A") (pinfunction "A_A") (pintype "passive"))
      (node (ref "R28") (pin "2") (pinfunction "2_2") (pintype "passive"))
    )
    (net (code "32") (name "Net-(HSMS-2824-BLKG-A1)") (class "Default")
      (node (ref "HSMS-2824-BLKG") (pin "1") (pinfunction "A1_1") (pintype "passive"))
      (node (ref "TO_BATTERY") (pin "3") (pinfunction "3_3") (pintype "passive"))
    )
    (net (code "33") (name "Net-(HSMS-2824-BLKG-C)") (class "Default")
      (node (ref "HSMS-2824-BLKG") (pin "3") (pinfunction "C_3") (pintype "passive"))
      (node (ref "S1") (pin "3") (pinfunction "S_3") (pintype "passive"))
      (node (ref "TVS13") (pin "A") (pinfunction "1_A") (pintype "passive"))
    )
    (net (code "34") (name "Net-(IC1-3V3OUT)") (class "Default")
      (node (ref "C17") (pin "1") (pinfunction "1_1") (pintype "passive"))
      (node (ref "IC1") (pin "10") (pinfunction "3V3OUT_10") (pintype "output"))
      (node (ref "IC1") (pin "11") (pinfunction "~{RESET}_11") (pintype "input"))
      (node (ref "IC1") (pin "3") (pinfunction "VCCIO_3") (pintype "power_in"))
    )
    (net (code "35") (name "Net-(IC1-CBUS1)") (class "Default")
      (node (ref "IC1") (pin "14") (pinfunction "CBUS1_14") (pintype "bidirectional"))
      (node (ref "RXLED") (pin "C") (pinfunction "C_C") (pintype "passive"))
    )
    (net (code "36") (name "Net-(IC1-CBUS2)") (class "Default")
      (node (ref "IC1") (pin "7") (pinfunction "CBUS2_7") (pintype "bidirectional"))
      (node (ref "TXLED") (pin "C") (pinfunction "C_C") (pintype "passive"))
    )
    (net (code "37") (name "Net-(IC1-USBDM)") (class "Default")
      (node (ref "IC1") (pin "9") (pinfunction "USBDM_9") (pintype "input"))
      (node (ref "R14") (pin "2") (pinfunction "2_2") (pintype "passive"))
    )
    (net (code "38") (name "Net-(IC1-USBDP)") (class "Default")
      (node (ref "IC1") (pin "8") (pinfunction "USBDP_8") (pintype "input"))
      (node (ref "R13") (pin "1") (pinfunction "1_1") (pintype "passive"))
    )
    (net (code "39") (name "Net-(R21-Pad1)") (class "Default")
      (node (ref "R21") (pin "1") (pinfunction "1_1") (pintype "passive"))
      (node (ref "R22") (pin "2") (pinfunction "2_2") (pintype "passive"))
      (node (ref "U2") (pin "CD1") (pinfunction "SHIELD_CD1") (pintype "bidirectional"))
      (node (ref "U2") (pin "CD2") (pinfunction "SHIELD_CD2") (pintype "bidirectional"))
    )
    (net (code "40") (name "Net-(R27-Pad2)") (class "Default")
      (node (ref "R27") (pin "2") (pinfunction "2_2") (pintype "passive"))
      (node (ref "TXLED") (pin "A") (pinfunction "A_A") (pintype "passive"))
    )
    (net (code "41") (name "Net-(R29-Pad1)") (class "Default")
      (node (ref "R29") (pin "1") (pinfunction "1_1") (pintype "passive"))
      (node (ref "RED") (pin "A") (pinfunction "A_A") (pintype "passive"))
    )
    (net (code "42") (name "Net-(R32-Pad1)") (class "Default")
      (node (ref "R32") (pin "1") (pinfunction "1_1") (pintype "passive"))
      (node (ref "RXLED") (pin "A") (pinfunction "A_A") (pintype "passive"))
    )
    (net (code "43") (name "Net-(S1-P)") (class "Default")
      (node (ref "C15") (pin "1") (pinfunction "1_1") (pintype "passive"))
      (node (ref "S1") (pin "2") (pinfunction "P_2") (pintype "passive"))
      (node (ref "TPS73233") (pin "1") (pinfunction "IN_1") (pintype "input"))
      (node (ref "TPS73233") (pin "3") (pinfunction "EN_3") (pintype "input"))
    )
    (net (code "44") (name "Net-(T1-D)") (class "Default")
      (node (ref "R11") (pin "1") (pinfunction "1_1") (pintype "passive"))
      (node (ref "R19") (pin "1") (pinfunction "1_1") (pintype "passive"))
      (node (ref "R20") (pin "1") (pinfunction "1_1") (pintype "passive"))
      (node (ref "R22") (pin "1") (pinfunction "1_1") (pintype "passive"))
      (node (ref "R24") (pin "1") (pinfunction "1_1") (pintype "passive"))
      (node (ref "R25") (pin "1") (pinfunction "1_1") (pintype "passive"))
      (node (ref "T1") (pin "1") (pinfunction "D_1") (pintype "passive"))
      (node (ref "U2") (pin "4") (pinfunction "VCC_4") (pintype "bidirectional"))
    )
    (net (code "45") (name "Net-(TPS73233-BP)") (class "Default")
      (node (ref "C14") (pin "1") (pinfunction "1_1") (pintype "passive"))
      (node (ref "TPS73233") (pin "4") (pinfunction "BP_4") (pintype "input"))
    )
    (net (code "46") (name "Net-(U1-PB8)") (class "Default")
      (node (ref "RED") (pin "C") (pinfunction "C_C") (pintype "passive"))
      (node (ref "U1") (pin "61") (pinfunction "PB8_61") (pintype "bidirectional"))
    )
    (net (code "47") (name "Net-(U1-PB9)") (class "Default")
      (node (ref "BLUE") (pin "C") (pinfunction "C_C") (pintype "passive"))
      (node (ref "U1") (pin "62") (pinfunction "PB9_62") (pintype "bidirectional"))
    )
    (net (code "48") (name "Net-(U1-PC15)") (class "Default")
      (node (ref "GREEN") (pin "C") (pinfunction "C_C") (pintype "passive"))
      (node (ref "U1") (pin "4") (pinfunction "PC15_4") (pintype "bidirectional"))
    )
    (net (code "49") (name "Net-(U1-PH0{slash}OSC_IN)") (class "Default")
      (node (ref "406C35E") (pin "1") (pinfunction "1_1") (pintype "passive"))
      (node (ref "C5") (pin "1") (pinfunction "1_1") (pintype "passive"))
      (node (ref "U1") (pin "5") (pinfunction "PH0/OSC_IN_5") (pintype "bidirectional"))
    )
    (net (code "50") (name "Net-(U1-PH1{slash}OSC_OUT)") (class "Default")
      (node (ref "R1") (pin "2") (pinfunction "2_2") (pintype "passive"))
      (node (ref "U1") (pin "6") (pinfunction "PH1/OSC_OUT_6") (pintype "bidirectional"))
    )
    (net (code "51") (name "Net-(U1-VBAT)") (class "Default")
      (node (ref "R23") (pin "2") (pinfunction "2_2") (pintype "passive"))
      (node (ref "SUPERCAP") (pin "+") (pinfunction "+_+") (pintype "passive"))
      (node (ref "U1") (pin "1") (pinfunction "VBAT_1") (pintype "power_in"))
    )
    (net (code "52") (name "Net-(U1-VCAP_1)") (class "Default")
      (node (ref "C1") (pin "1") (pinfunction "1_1") (pintype "passive"))
      (node (ref "U1") (pin "31") (pinfunction "VCAP_1_31") (pintype "power_in"))
    )
    (net (code "53") (name "Net-(U1-VCAP_2)") (class "Default")
      (node (ref "C2") (pin "1") (pinfunction "1_1") (pintype "passive"))
      (node (ref "U1") (pin "47") (pinfunction "VCAP_2_47") (pintype "power_in"))
    )
    (net (code "54") (name "PROGRAMMING_EN") (class "Default")
      (node (ref "PROGRAM") (pin "1") (pinfunction "1_1") (pintype "passive"))
      (node (ref "PROGRAM") (pin "2") (pinfunction "2_2") (pintype "passive"))
      (node (ref "U1") (pin "33") (pinfunction "PB12_33") (pintype "bidirectional"))
    )
    (net (code "55") (name "RED") (class "Default")
      (node (ref "ADC_SEN3") (pin "2") (pinfunction "2_2") (pintype "passive"))
      (node (ref "TVS9") (pin "A") (pinfunction "1_A") (pintype "passive"))
      (node (ref "U1") (pin "15") (pinfunction "PA1_15") (pintype "bidirectional"))
    )
    (net (code "56") (name "RESET") (class "Default")
      (node (ref "C6") (pin "1") (pinfunction "1_1") (pintype "passive"))
      (node (ref "RESET") (pin "3") (pinfunction "3_3") (pintype "passive"))
      (node (ref "RESET") (pin "4") (pinfunction "4_4") (pintype "passive"))
      (node (ref "SWD_DEBUG_PORT") (pin "10") (pinfunction "10_10") (pintype "passive"))
      (node (ref "TP4") (pin "TP") (pinfunction "TP_TP") (pintype "input"))
      (node (ref "U1") (pin "7") (pinfunction "NRST_7") (pintype "power_in"))
    )
    (net (code "57") (name "SDIO_CK") (class "Default")
      (node (ref "U1") (pin "53") (pinfunction "PC12_53") (pintype "bidirectional"))
      (node (ref "U2") (pin "5") (pinfunction "SCK_5") (pintype "bidirectional"))
    )
    (net (code "58") (name "SDIO_CMD") (class "Default")
      (node (ref "R20") (pin "2") (pinfunction "2_2") (pintype "passive"))
      (node (ref "U1") (pin "54") (pinfunction "PD2_54") (pintype "bidirectional"))
      (node (ref "U2") (pin "3") (pinfunction "DI_3") (pintype "bidirectional"))
    )
    (net (code "59") (name "SDIO_D0") (class "Default")
      (node (ref "R11") (pin "2") (pinfunction "2_2") (pintype "passive"))
      (node (ref "U1") (pin "39") (pinfunction "PC8_39") (pintype "bidirectional"))
      (node (ref "U2") (pin "7") (pinfunction "DO_7") (pintype "bidirectional"))
    )
    (net (code "60") (name "SDIO_D1") (class "Default")
      (node (ref "R25") (pin "2") (pinfunction "2_2") (pintype "passive"))
      (node (ref "U1") (pin "40") (pinfunction "PC9_40") (pintype "bidirectional"))
      (node (ref "U2") (pin "8") (pinfunction "RSV_8") (pintype "bidirectional"))
    )
    (net (code "61") (name "SDIO_D2") (class "Default")
      (node (ref "R19") (pin "2") (pinfunction "2_2") (pintype "passive"))
      (node (ref "U1") (pin "51") (pinfunction "PC10_51") (pintype "bidirectional"))
      (node (ref "U2") (pin "1") (pinfunction "NC_1") (pintype "bidirectional"))
    )
    (net (code "62") (name "SDIO_D3") (class "Default")
      (node (ref "R24") (pin "2") (pinfunction "2_2") (pintype "passive"))
      (node (ref "U1") (pin "52") (pinfunction "PC11_52") (pintype "bidirectional"))
      (node (ref "U2") (pin "2") (pinfunction "CS_2") (pintype "bidirectional"))
    )
    (net (code "63") (name "SD_DETECT") (class "Default")
      (node (ref "R21") (pin "2") (pinfunction "2_2") (pintype "passive"))
      (node (ref "U1") (pin "25") (pinfunction "PC5_25") (pintype "bidirectional"))
    )
    (net (code "64") (name "SD_EJECT") (class "Default")
      (node (ref "EJECT") (pin "1") (pinfunction "1_1") (pintype "passive"))
      (node (ref "EJECT") (pin "2") (pinfunction "2_2") (pintype "passive"))
      (node (ref "U1") (pin "24") (pinfunction "PC4_24") (pintype "bidirectional"))
    )
    (net (code "65") (name "SD_PWR_EN") (class "Default")
      (node (ref "R10") (pin "2") (pinfunction "2_2") (pintype "passive"))
      (node (ref "T1") (pin "3") (pinfunction "G_3") (pintype "passive"))
      (node (ref "U1") (pin "23") (pinfunction "PA7_23") (pintype "bidirectional"))
    )
    (net (code "66") (name "SWCK") (class "Default")
      (node (ref "SWD_DEBUG_PORT") (pin "4") (pinfunction "4_4") (pintype "passive"))
      (node (ref "TP3") (pin "TP") (pinfunction "TP_TP") (pintype "input"))
      (node (ref "U1") (pin "49") (pinfunction "JTCK/SWCLK/PA14_49") (pintype "bidirectional"))
    )
    (net (code "67") (name "SWDIO") (class "Default")
      (node (ref "R6") (pin "1") (pinfunction "1_1") (pintype "passive"))
      (node (ref "SWD_DEBUG_PORT") (pin "2") (pinfunction "2_2") (pintype "passive"))
      (node (ref "TP1") (pin "TP") (pinfunction "TP_TP") (pintype "input"))
      (node (ref "U1") (pin "46") (pinfunction "JTMS/SWDIO/PA13_46") (pintype "bidirectional"))
    )
    (net (code "68") (name "USART3_RX") (class "Default")
      (node (ref "IC1") (pin "4") (pinfunction "RXD_4") (pintype "input"))
      (node (ref "R31") (pin "1") (pinfunction "1_1") (pintype "passive"))
      (node (ref "U1") (pin "29") (pinfunction "PB10_29") (pintype "bidirectional"))
    )
    (net (code "69") (name "USART3_TX") (class "Default")
      (node (ref "IC1") (pin "1") (pinfunction "TXD_1") (pintype "output"))
      (node (ref "R33") (pin "1") (pinfunction "1_1") (pintype "passive"))
      (node (ref "U1") (pin "30") (pinfunction "PB11_30") (pintype "bidirectional"))
    )
    (net (code "70") (name "USB{slash}FS_OVERCURRENT") (class "Default")
      (node (ref "2141") (pin "3") (pinfunction "FAULT_3") (pintype "bidirectional"))
      (node (ref "R16") (pin "1") (pinfunction "1_1") (pintype "passive"))
      (node (ref "TP2") (pin "TP") (pinfunction "TP_TP") (pintype "input"))
      (node (ref "U1") (pin "10") (pinfunction "PC2_10") (pintype "bidirectional"))
    )
    (net (code "71") (name "USB{slash}FS_POWERSWITCHON") (class "Default")
      (node (ref "2141") (pin "4") (pinfunction "EN_4") (pintype "bidirectional"))
      (node (ref "R15") (pin "1") (pinfunction "1_1") (pintype "passive"))
      (node (ref "U1") (pin "57") (pinfunction "PB5_57") (pintype "bidirectional"))
    )
    (net (code "72") (name "VBUS{slash}FS") (class "Default")
      (node (ref "2141") (pin "1") (pinfunction "OUT_1") (pintype "bidirectional"))
      (node (ref "C16") (pin "1") (pinfunction "1_1") (pintype "passive"))
      (node (ref "C20") (pin "1") (pinfunction "1_1") (pintype "passive"))
      (node (ref "HSMS-2824-BLKG") (pin "2") (pinfunction "A2_2") (pintype "passive"))
      (node (ref "IC1") (pin "12") (pinfunction "VCC_12") (pintype "power_in"))
      (node (ref "RCLAMP") (pin "5") (pinfunction "5_5") (pintype "bidirectional"))
      (node (ref "TO_BATTERY") (pin "2") (pinfunction "2_2") (pintype "passive"))
      (node (ref "U1") (pin "42") (pinfunction "PA9_42") (pintype "bidirectional"))
    )
    (net (code "73") (name "VBUS{slash}FS_IN") (class "Default")
      (node (ref "2141") (pin "5") (pinfunction "IN_5") (pintype "bidirectional"))
      (node (ref "C21") (pin "1") (pinfunction "1_1") (pintype "passive"))
      (node (ref "USBTOUART") (pin "1") (pinfunction "1_1") (pintype "input"))
      (node (ref "USB_FS") (pin "1") (pinfunction "1_1") (pintype "input"))
    )
    (net (code "74") (name "unconnected-(IC1-CBUS0-Pad15)") (class "Default")
      (node (ref "IC1") (pin "15") (pinfunction "CBUS0_15") (pintype "bidirectional"))
    )
    (net (code "75") (name "unconnected-(IC1-CBUS3-Pad16)") (class "Default")
      (node (ref "IC1") (pin "16") (pinfunction "CBUS3_16") (pintype "bidirectional"))
    )
    (net (code "76") (name "unconnected-(IC1-~{CTS}-Pad6)") (class "Default")
      (node (ref "IC1") (pin "6") (pinfunction "~{CTS}_6") (pintype "input"))
    )
    (net (code "77") (name "unconnected-(IC1-~{RTS}-Pad2)") (class "Default")
      (node (ref "IC1") (pin "2") (pinfunction "~{RTS}_2") (pintype "output"))
    )
    (net (code "78") (name "unconnected-(RCLAMP-Pad1)") (class "Default")
      (node (ref "RCLAMP") (pin "1") (pinfunction "1_1") (pintype "bidirectional"))
    )
    (net (code "79") (name "unconnected-(RCLAMP-Pad6)") (class "Default")
      (node (ref "RCLAMP") (pin "6") (pinfunction "6_6") (pintype "bidirectional"))
    )
    (net (code "80") (name "unconnected-(SWD_DEBUG_PORT-Pad6)") (class "Default")
      (node (ref "SWD_DEBUG_PORT") (pin "6") (pinfunction "6_6") (pintype "passive"))
    )
    (net (code "81") (name "unconnected-(SWD_DEBUG_PORT-Pad7)") (class "Default")
      (node (ref "SWD_DEBUG_PORT") (pin "7") (pinfunction "7_7") (pintype "passive"))
    )
    (net (code "82") (name "unconnected-(SWD_DEBUG_PORT-Pad8)") (class "Default")
      (node (ref "SWD_DEBUG_PORT") (pin "8") (pinfunction "8_8") (pintype "passive"))
    )
    (net (code "83") (name "unconnected-(U1-JTDI{slash}PA15-Pad50)") (class "Default")
      (node (ref "U1") (pin "50") (pinfunction "JTDI/PA15_50") (pintype "bidirectional"))
    )
    (net (code "84") (name "unconnected-(U1-JTDO{slash}TRACESSW0{slash}PB3-Pad55)") (class "Default")
      (node (ref "U1") (pin "55") (pinfunction "JTDO/TRACESSW0/PB3_55") (pintype "bidirectional"))
    )
    (net (code "85") (name "unconnected-(U1-NJTRST{slash}PB4-Pad56)") (class "Default")
      (node (ref "U1") (pin "56") (pinfunction "NJTRST/PB4_56") (pintype "bidirectional"))
    )
    (net (code "86") (name "unconnected-(U1-PA4-Pad20)") (class "Default")
      (node (ref "U1") (pin "20") (pinfunction "PA4_20") (pintype "bidirectional"))
    )
    (net (code "87") (name "unconnected-(U1-PA5-Pad21)") (class "Default")
      (node (ref "U1") (pin "21") (pinfunction "PA5_21") (pintype "bidirectional"))
    )
    (net (code "88") (name "unconnected-(U1-PB0-Pad26)") (class "Default")
      (node (ref "U1") (pin "26") (pinfunction "PB0_26") (pintype "bidirectional"))
    )
    (net (code "89") (name "unconnected-(U1-PB1-Pad27)") (class "Default")
      (node (ref "U1") (pin "27") (pinfunction "PB1_27") (pintype "bidirectional"))
    )
    (net (code "90") (name "unconnected-(U1-PB2-Pad28)") (class "Default")
      (node (ref "U1") (pin "28") (pinfunction "PB2_28") (pintype "bidirectional"))
    )
    (net (code "91") (name "unconnected-(U1-PB15-Pad36)") (class "Default")
      (node (ref "U1") (pin "36") (pinfunction "PB15_36") (pintype "bidirectional"))
    )
    (net (code "92") (name "unconnected-(U1-PC1-Pad9)") (class "Default")
      (node (ref "U1") (pin "9") (pinfunction "PC1_9") (pintype "bidirectional"))
    )
    (net (code "93") (name "unconnected-(U1-PC3-Pad11)") (class "Default")
      (node (ref "U1") (pin "11") (pinfunction "PC3_11") (pintype "bidirectional"))
    )
    (net (code "94") (name "unconnected-(U1-PC6-Pad37)") (class "Default")
      (node (ref "U1") (pin "37") (pinfunction "PC6_37") (pintype "bidirectional"))
    )
    (net (code "95") (name "unconnected-(U1-PC7-Pad38)") (class "Default")
      (node (ref "U1") (pin "38") (pinfunction "PC7_38") (pintype "bidirectional"))
    )
    (net (code "96") (name "unconnected-(U1-PC13-Pad2)") (class "Default")
      (node (ref "U1") (pin "2") (pinfunction "PC13_2") (pintype "bidirectional"))
    )
    (net (code "97") (name "unconnected-(U1-PC14-Pad3)") (class "Default")
      (node (ref "U1") (pin "3") (pinfunction "PC14_3") (pintype "bidirectional"))
    )
    (net (code "98") (name "unconnected-(U1-WKUP{slash}PA0-Pad14)") (class "Default")
      (node (ref "U1") (pin "14") (pinfunction "WKUP/PA0_14") (pintype "bidirectional"))
    )
    (net (code "99") (name "unconnected-(USBTOUART-Pad4)") (class "Default")
      (node (ref "USBTOUART") (pin "4") (pinfunction "4_4") (pintype "input"))
    )
    (net (code "100") (name "unconnected-(USB_FS-Pad4)") (class "Default")
      (node (ref "USB_FS") (pin "4") (pinfunction "4_4") (pintype "input"))
    )
  )
)
